# DI_220V_DC.net
KiCad netlist of a schematic drawn in Altium Designer
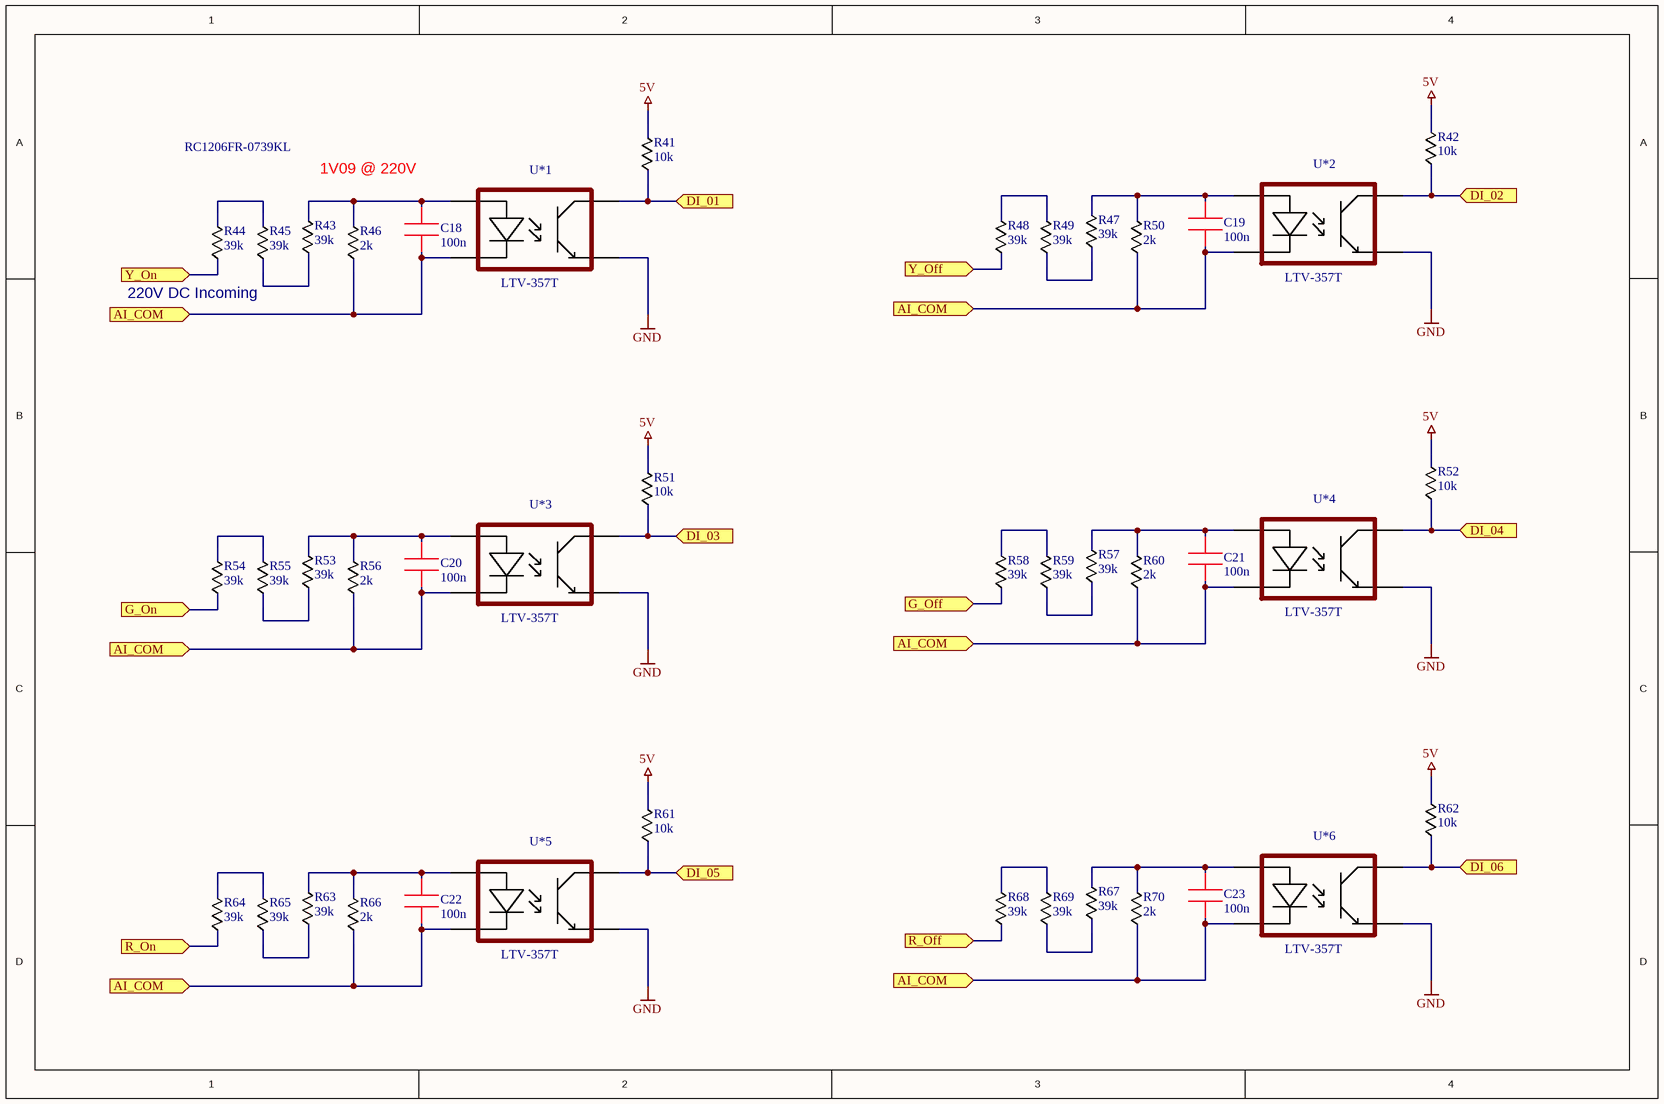
[diagram p0: DI 220V DC.SchDoc]

(export (version "E")
  (design (tool "Eeschema 10.0.6"))
  (components
    (comp (ref "C18")
      (value "100n")
      (footprint "0603")
      (description "CC0603KRX7R9BB104")
      (libsource (lib "kontr") (part "0603 CAP"))
    )
    (comp (ref "C19")
      (value "100n")
      (footprint "0603")
      (description "CC0603KRX7R9BB104")
      (libsource (lib "kontr") (part "0603 CAP"))
    )
    (comp (ref "C20")
      (value "100n")
      (footprint "0603")
      (description "CC0603KRX7R9BB104")
      (libsource (lib "kontr") (part "0603 CAP"))
    )
    (comp (ref "C21")
      (value "100n")
      (footprint "0603")
      (description "CC0603KRX7R9BB104")
      (libsource (lib "kontr") (part "0603 CAP"))
    )
    (comp (ref "C22")
      (value "100n")
      (footprint "0603")
      (description "CC0603KRX7R9BB104")
      (libsource (lib "kontr") (part "0603 CAP"))
    )
    (comp (ref "C23")
      (value "100n")
      (footprint "0603")
      (description "CC0603KRX7R9BB104")
      (libsource (lib "kontr") (part "0603 CAP"))
    )
    (comp (ref "R41")
      (value "10k")
      (footprint "0603")
      (description "RC0603FR-0710KL")
      (libsource (lib "kontr") (part "0603 RES"))
    )
    (comp (ref "R42")
      (value "10k")
      (footprint "0603")
      (description "RC0603FR-0710KL")
      (libsource (lib "kontr") (part "0603 RES"))
    )
    (comp (ref "R43")
      (value "39k")
      (footprint "1206")
      (description "RC1206FR-0739KL")
      (libsource (lib "kontr") (part "1206 R"))
    )
    (comp (ref "R44")
      (value "39k")
      (footprint "1206")
      (description "RC1206FR-0739KL")
      (libsource (lib "kontr") (part "1206 R"))
    )
    (comp (ref "R45")
      (value "39k")
      (footprint "1206")
      (description "RC1206FR-0739KL")
      (libsource (lib "kontr") (part "1206 R"))
    )
    (comp (ref "R46")
      (value "2k")
      (footprint "1206")
      (description "RC1206FR-072KL")
      (libsource (lib "kontr") (part "1206 R"))
    )
    (comp (ref "R47")
      (value "39k")
      (footprint "1206")
      (description "RC1206FR-0739KL")
      (libsource (lib "kontr") (part "1206 R"))
    )
    (comp (ref "R48")
      (value "39k")
      (footprint "1206")
      (description "RC1206FR-0739KL")
      (libsource (lib "kontr") (part "1206 R"))
    )
    (comp (ref "R49")
      (value "39k")
      (footprint "1206")
      (description "RC1206FR-0739KL")
      (libsource (lib "kontr") (part "1206 R"))
    )
    (comp (ref "R50")
      (value "2k")
      (footprint "1206")
      (description "RC1206FR-072KL")
      (libsource (lib "kontr") (part "1206 R"))
    )
    (comp (ref "R51")
      (value "10k")
      (footprint "0603")
      (description "RC0603FR-0710KL")
      (libsource (lib "kontr") (part "0603 RES"))
    )
    (comp (ref "R52")
      (value "10k")
      (footprint "0603")
      (description "RC0603FR-0710KL")
      (libsource (lib "kontr") (part "0603 RES"))
    )
    (comp (ref "R53")
      (value "39k")
      (footprint "1206")
      (description "RC1206FR-0739KL")
      (libsource (lib "kontr") (part "1206 R"))
    )
    (comp (ref "R54")
      (value "39k")
      (footprint "1206")
      (description "RC1206FR-0739KL")
      (libsource (lib "kontr") (part "1206 R"))
    )
    (comp (ref "R55")
      (value "39k")
      (footprint "1206")
      (description "RC1206FR-0739KL")
      (libsource (lib "kontr") (part "1206 R"))
    )
    (comp (ref "R56")
      (value "2k")
      (footprint "1206")
      (description "RC1206FR-072KL")
      (libsource (lib "kontr") (part "1206 R"))
    )
    (comp (ref "R57")
      (value "39k")
      (footprint "1206")
      (description "RC1206FR-0739KL")
      (libsource (lib "kontr") (part "1206 R"))
    )
    (comp (ref "R58")
      (value "39k")
      (footprint "1206")
      (description "RC1206FR-0739KL")
      (libsource (lib "kontr") (part "1206 R"))
    )
    (comp (ref "R59")
      (value "39k")
      (footprint "1206")
      (description "RC1206FR-0739KL")
      (libsource (lib "kontr") (part "1206 R"))
    )
    (comp (ref "R60")
      (value "2k")
      (footprint "1206")
      (description "RC1206FR-072KL")
      (libsource (lib "kontr") (part "1206 R"))
    )
    (comp (ref "R61")
      (value "10k")
      (footprint "0603")
      (description "RC0603FR-0710KL")
      (libsource (lib "kontr") (part "0603 RES"))
    )
    (comp (ref "R62")
      (value "10k")
      (footprint "0603")
      (description "RC0603FR-0710KL")
      (libsource (lib "kontr") (part "0603 RES"))
    )
    (comp (ref "R63")
      (value "39k")
      (footprint "1206")
      (description "RC1206FR-0739KL")
      (libsource (lib "kontr") (part "1206 R"))
    )
    (comp (ref "R64")
      (value "39k")
      (footprint "1206")
      (description "RC1206FR-0739KL")
      (libsource (lib "kontr") (part "1206 R"))
    )
    (comp (ref "R65")
      (value "39k")
      (footprint "1206")
      (description "RC1206FR-0739KL")
      (libsource (lib "kontr") (part "1206 R"))
    )
    (comp (ref "R66")
      (value "2k")
      (footprint "1206")
      (description "RC1206FR-072KL")
      (libsource (lib "kontr") (part "1206 R"))
    )
    (comp (ref "R67")
      (value "39k")
      (footprint "1206")
      (description "RC1206FR-0739KL")
      (libsource (lib "kontr") (part "1206 R"))
    )
    (comp (ref "R68")
      (value "39k")
      (footprint "1206")
      (description "RC1206FR-0739KL")
      (libsource (lib "kontr") (part "1206 R"))
    )
    (comp (ref "R69")
      (value "39k")
      (footprint "1206")
      (description "RC1206FR-0739KL")
      (libsource (lib "kontr") (part "1206 R"))
    )
    (comp (ref "R70")
      (value "2k")
      (footprint "1206")
      (description "RC1206FR-072KL")
      (libsource (lib "kontr") (part "1206 R"))
    )
    (comp (ref "U*1")
      (value "LTV-357T")
      (footprint "levin:SOP-4")
      (libsource (lib "levin") (part "LTV-357T"))
    )
    (comp (ref "U*2")
      (value "LTV-357T")
      (footprint "levin:SOP-4")
      (libsource (lib "levin") (part "LTV-357T"))
    )
    (comp (ref "U*3")
      (value "LTV-357T")
      (footprint "levin:SOP-4")
      (libsource (lib "levin") (part "LTV-357T"))
    )
    (comp (ref "U*4")
      (value "LTV-357T")
      (footprint "levin:SOP-4")
      (libsource (lib "levin") (part "LTV-357T"))
    )
    (comp (ref "U*5")
      (value "LTV-357T")
      (footprint "levin:SOP-4")
      (libsource (lib "levin") (part "LTV-357T"))
    )
    (comp (ref "U*6")
      (value "LTV-357T")
      (footprint "levin:SOP-4")
      (libsource (lib "levin") (part "LTV-357T"))
    )
  )
  (nets
    (net (code "1") (name "/AI_COM") (class "Default")
      (node (ref "C18") (pin "1") (pinfunction "1_1") (pintype "passive"))
      (node (ref "C19") (pin "1") (pinfunction "1_1") (pintype "passive"))
      (node (ref "C20") (pin "1") (pinfunction "1_1") (pintype "passive"))
      (node (ref "C21") (pin "1") (pinfunction "1_1") (pintype "passive"))
      (node (ref "C22") (pin "1") (pinfunction "1_1") (pintype "passive"))
      (node (ref "C23") (pin "1") (pinfunction "1_1") (pintype "passive"))
      (node (ref "R46") (pin "1") (pintype "passive"))
      (node (ref "R50") (pin "1") (pintype "passive"))
      (node (ref "R56") (pin "1") (pintype "passive"))
      (node (ref "R60") (pin "1") (pintype "passive"))
      (node (ref "R66") (pin "1") (pintype "passive"))
      (node (ref "R70") (pin "1") (pintype "passive"))
      (node (ref "U*1") (pin "Cathode") (pinfunction "C_Cathode") (pintype "passive"))
      (node (ref "U*2") (pin "Cathode") (pinfunction "C_Cathode") (pintype "passive"))
      (node (ref "U*3") (pin "Cathode") (pinfunction "C_Cathode") (pintype "passive"))
      (node (ref "U*4") (pin "Cathode") (pinfunction "C_Cathode") (pintype "passive"))
      (node (ref "U*5") (pin "Cathode") (pinfunction "C_Cathode") (pintype "passive"))
      (node (ref "U*6") (pin "Cathode") (pinfunction "C_Cathode") (pintype "passive"))
    )
    (net (code "2") (name "/DI_01") (class "Default")
      (node (ref "R41") (pin "1") (pintype "passive"))
      (node (ref "U*1") (pin "Collector") (pinfunction "C_Collector") (pintype "passive"))
    )
    (net (code "3") (name "/DI_02") (class "Default")
      (node (ref "R42") (pin "1") (pintype "passive"))
      (node (ref "U*2") (pin "Collector") (pinfunction "C_Collector") (pintype "passive"))
    )
    (net (code "4") (name "/DI_03") (class "Default")
      (node (ref "R51") (pin "1") (pintype "passive"))
      (node (ref "U*3") (pin "Collector") (pinfunction "C_Collector") (pintype "passive"))
    )
    (net (code "5") (name "/DI_04") (class "Default")
      (node (ref "R52") (pin "1") (pintype "passive"))
      (node (ref "U*4") (pin "Collector") (pinfunction "C_Collector") (pintype "passive"))
    )
    (net (code "6") (name "/DI_05") (class "Default")
      (node (ref "R61") (pin "1") (pintype "passive"))
      (node (ref "U*5") (pin "Collector") (pinfunction "C_Collector") (pintype "passive"))
    )
    (net (code "7") (name "/DI_06") (class "Default")
      (node (ref "R62") (pin "1") (pintype "passive"))
      (node (ref "U*6") (pin "Collector") (pinfunction "C_Collector") (pintype "passive"))
    )
    (net (code "8") (name "/G_Off") (class "Default") (node (ref "R58") (pin "1") (pintype "passive")))
    (net (code "9") (name "/G_On") (class "Default") (node (ref "R54") (pin "1") (pintype "passive")))
    (net (code "10") (name "/R_Off") (class "Default") (node (ref "R68") (pin "1") (pintype "passive")))
    (net (code "11") (name "/R_On") (class "Default") (node (ref "R64") (pin "1") (pintype "passive")))
    (net (code "12") (name "/Y_Off") (class "Default") (node (ref "R48") (pin "1") (pintype "passive")))
    (net (code "13") (name "/Y_On") (class "Default") (node (ref "R44") (pin "1") (pintype "passive")))
    (net (code "14") (name "5V") (class "Default")
      (node (ref "R41") (pin "2") (pintype "passive"))
      (node (ref "R42") (pin "2") (pintype "passive"))
      (node (ref "R51") (pin "2") (pintype "passive"))
      (node (ref "R52") (pin "2") (pintype "passive"))
      (node (ref "R61") (pin "2") (pintype "passive"))
      (node (ref "R62") (pin "2") (pintype "passive"))
    )
    (net (code "15") (name "GND") (class "Default")
      (node (ref "U*1") (pin "Emmiter") (pinfunction "E_Emmiter") (pintype "passive"))
      (node (ref "U*2") (pin "Emmiter") (pinfunction "E_Emmiter") (pintype "passive"))
      (node (ref "U*3") (pin "Emmiter") (pinfunction "E_Emmiter") (pintype "passive"))
      (node (ref "U*4") (pin "Emmiter") (pinfunction "E_Emmiter") (pintype "passive"))
      (node (ref "U*5") (pin "Emmiter") (pinfunction "E_Emmiter") (pintype "passive"))
      (node (ref "U*6") (pin "Emmiter") (pinfunction "E_Emmiter") (pintype "passive"))
    )
    (net (code "16") (name "Net-(R43-Pad1)") (class "Default")
      (node (ref "R43") (pin "1") (pintype "passive"))
      (node (ref "R45") (pin "1") (pintype "passive"))
    )
    (net (code "17") (name "Net-(R44-Pad2)") (class "Default")
      (node (ref "R44") (pin "2") (pintype "passive"))
      (node (ref "R45") (pin "2") (pintype "passive"))
    )
    (net (code "18") (name "Net-(R47-Pad1)") (class "Default")
      (node (ref "R47") (pin "1") (pintype "passive"))
      (node (ref "R49") (pin "1") (pintype "passive"))
    )
    (net (code "19") (name "Net-(R48-Pad2)") (class "Default")
      (node (ref "R48") (pin "2") (pintype "passive"))
      (node (ref "R49") (pin "2") (pintype "passive"))
    )
    (net (code "20") (name "Net-(R53-Pad1)") (class "Default")
      (node (ref "R53") (pin "1") (pintype "passive"))
      (node (ref "R55") (pin "1") (pintype "passive"))
    )
    (net (code "21") (name "Net-(R54-Pad2)") (class "Default")
      (node (ref "R54") (pin "2") (pintype "passive"))
      (node (ref "R55") (pin "2") (pintype "passive"))
    )
    (net (code "22") (name "Net-(R57-Pad1)") (class "Default")
      (node (ref "R57") (pin "1") (pintype "passive"))
      (node (ref "R59") (pin "1") (pintype "passive"))
    )
    (net (code "23") (name "Net-(R58-Pad2)") (class "Default")
      (node (ref "R58") (pin "2") (pintype "passive"))
      (node (ref "R59") (pin "2") (pintype "passive"))
    )
    (net (code "24") (name "Net-(R63-Pad1)") (class "Default")
      (node (ref "R63") (pin "1") (pintype "passive"))
      (node (ref "R65") (pin "1") (pintype "passive"))
    )
    (net (code "25") (name "Net-(R64-Pad2)") (class "Default")
      (node (ref "R64") (pin "2") (pintype "passive"))
      (node (ref "R65") (pin "2") (pintype "passive"))
    )
    (net (code "26") (name "Net-(R67-Pad1)") (class "Default")
      (node (ref "R67") (pin "1") (pintype "passive"))
      (node (ref "R69") (pin "1") (pintype "passive"))
    )
    (net (code "27") (name "Net-(R68-Pad2)") (class "Default")
      (node (ref "R68") (pin "2") (pintype "passive"))
      (node (ref "R69") (pin "2") (pintype "passive"))
    )
    (net (code "28") (name "Net-(U*1-A)") (class "Default")
      (node (ref "C18") (pin "2") (pinfunction "2_2") (pintype "passive"))
      (node (ref "R43") (pin "2") (pintype "passive"))
      (node (ref "R46") (pin "2") (pintype "passive"))
      (node (ref "U*1") (pin "Anode") (pinfunction "A_Anode") (pintype "passive"))
    )
    (net (code "29") (name "Net-(U*2-A)") (class "Default")
      (node (ref "C19") (pin "2") (pinfunction "2_2") (pintype "passive"))
      (node (ref "R47") (pin "2") (pintype "passive"))
      (node (ref "R50") (pin "2") (pintype "passive"))
      (node (ref "U*2") (pin "Anode") (pinfunction "A_Anode") (pintype "passive"))
    )
    (net (code "30") (name "Net-(U*3-A)") (class "Default")
      (node (ref "C20") (pin "2") (pinfunction "2_2") (pintype "passive"))
      (node (ref "R53") (pin "2") (pintype "passive"))
      (node (ref "R56") (pin "2") (pintype "passive"))
      (node (ref "U*3") (pin "Anode") (pinfunction "A_Anode") (pintype "passive"))
    )
    (net (code "31") (name "Net-(U*4-A)") (class "Default")
      (node (ref "C21") (pin "2") (pinfunction "2_2") (pintype "passive"))
      (node (ref "R57") (pin "2") (pintype "passive"))
      (node (ref "R60") (pin "2") (pintype "passive"))
      (node (ref "U*4") (pin "Anode") (pinfunction "A_Anode") (pintype "passive"))
    )
    (net (code "32") (name "Net-(U*5-A)") (class "Default")
      (node (ref "C22") (pin "2") (pinfunction "2_2") (pintype "passive"))
      (node (ref "R63") (pin "2") (pintype "passive"))
      (node (ref "R66") (pin "2") (pintype "passive"))
      (node (ref "U*5") (pin "Anode") (pinfunction "A_Anode") (pintype "passive"))
    )
    (net (code "33") (name "Net-(U*6-A)") (class "Default")
      (node (ref "C23") (pin "2") (pinfunction "2_2") (pintype "passive"))
      (node (ref "R67") (pin "2") (pintype "passive"))
      (node (ref "R70") (pin "2") (pintype "passive"))
      (node (ref "U*6") (pin "Anode") (pinfunction "A_Anode") (pintype "passive"))
    )
  )
)
